# Microcontroller.net
KiCad netlist of a schematic drawn in Altium Designer
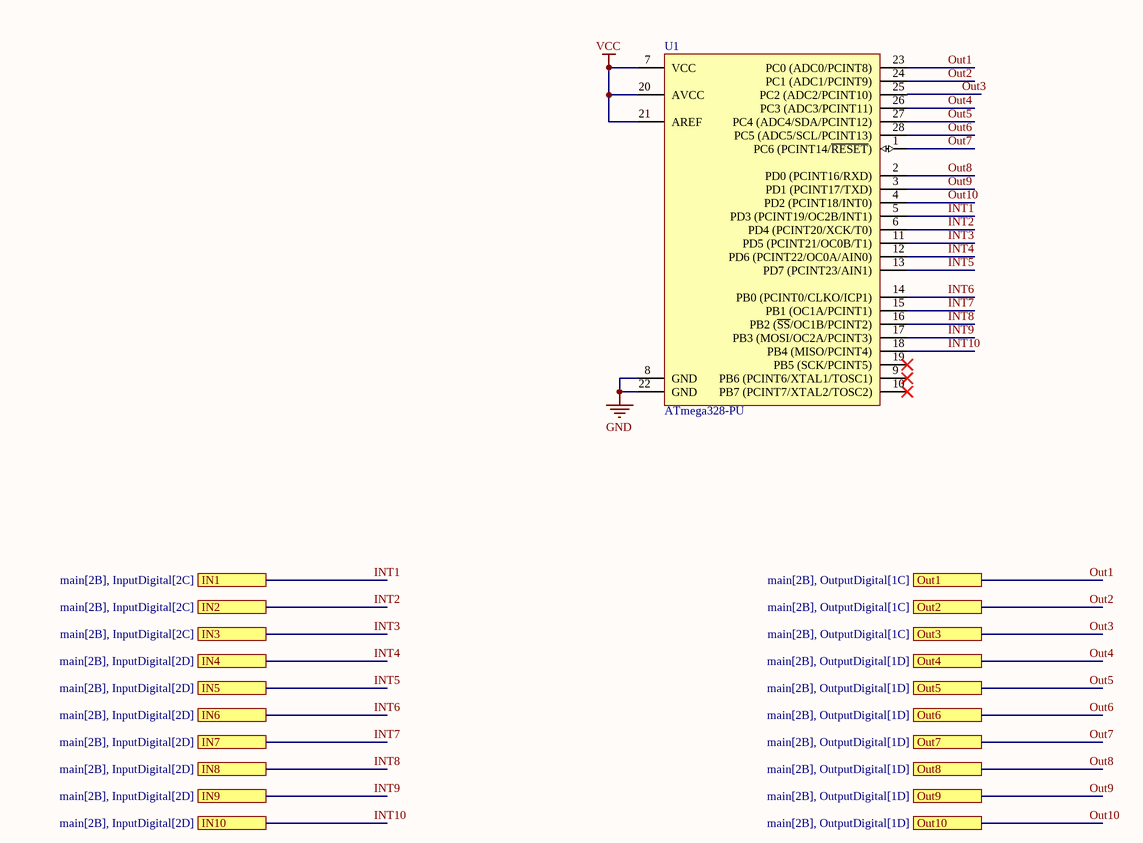
[diagram p0: Microcontroller.SchDoc]

(export (version "E")
  (design (tool "Eeschema 10.0.6"))
  (components
    (comp (ref "U1")
      (value "ATmega328-PU")
      (footprint "28P3")
      (libsource (lib "Ejemplo2") (part "CMP-0095-00015-2"))
    )
  )
  (nets
    (net (code "1") (name "/INT1") (class "Default")
      (node (ref "U1") (pin "5") (pinfunction "PD3_(PCINT19/OC2B/INT1)_5") (pintype "passive"))
    )
    (net (code "2") (name "/INT2") (class "Default")
      (node (ref "U1") (pin "6") (pinfunction "PD4_(PCINT20/XCK/T0)_6") (pintype "passive"))
    )
    (net (code "3") (name "/INT3") (class "Default")
      (node (ref "U1") (pin "11") (pinfunction "PD5_(PCINT21/OC0B/T1)_11") (pintype "passive"))
    )
    (net (code "4") (name "/INT4") (class "Default")
      (node (ref "U1") (pin "12") (pinfunction "PD6_(PCINT22/OC0A/AIN0)_12") (pintype "passive"))
    )
    (net (code "5") (name "/INT5") (class "Default")
      (node (ref "U1") (pin "13") (pinfunction "PD7_(PCINT23/AIN1)_13") (pintype "passive"))
    )
    (net (code "6") (name "/INT6") (class "Default")
      (node (ref "U1") (pin "14") (pinfunction "PB0_(PCINT0/CLKO/ICP1)_14") (pintype "passive"))
    )
    (net (code "7") (name "/INT7") (class "Default")
      (node (ref "U1") (pin "15") (pinfunction "PB1_(OC1A/PCINT1)_15") (pintype "passive"))
    )
    (net (code "8") (name "/INT8") (class "Default")
      (node (ref "U1") (pin "16") (pinfunction "PB2_(~{SS}/OC1B/PCINT2)_16") (pintype "passive"))
    )
    (net (code "9") (name "/INT9") (class "Default")
      (node (ref "U1") (pin "17") (pinfunction "PB3_(MOSI/OC2A/PCINT3)_17") (pintype "passive"))
    )
    (net (code "10") (name "/INT10") (class "Default")
      (node (ref "U1") (pin "18") (pinfunction "PB4_(MISO/PCINT4)_18") (pintype "passive"))
    )
    (net (code "11") (name "/Out1") (class "Default")
      (node (ref "U1") (pin "23") (pinfunction "PC0_(ADC0/PCINT8)_23") (pintype "passive"))
    )
    (net (code "12") (name "/Out2") (class "Default")
      (node (ref "U1") (pin "24") (pinfunction "PC1_(ADC1/PCINT9)_24") (pintype "passive"))
    )
    (net (code "13") (name "/Out3") (class "Default")
      (node (ref "U1") (pin "25") (pinfunction "PC2_(ADC2/PCINT10)_25") (pintype "passive"))
    )
    (net (code "14") (name "/Out4") (class "Default")
      (node (ref "U1") (pin "26") (pinfunction "PC3_(ADC3/PCINT11)_26") (pintype "passive"))
    )
    (net (code "15") (name "/Out5") (class "Default")
      (node (ref "U1") (pin "27") (pinfunction "PC4_(ADC4/SDA/PCINT12)_27") (pintype "passive"))
    )
    (net (code "16") (name "/Out6") (class "Default")
      (node (ref "U1") (pin "28") (pinfunction "PC5_(ADC5/SCL/PCINT13)_28") (pintype "passive"))
    )
    (net (code "17") (name "/Out7") (class "Default")
      (node (ref "U1") (pin "1") (pinfunction "PC6_(PCINT14/~{RESET})_1") (pintype "bidirectional"))
    )
    (net (code "18") (name "/Out8") (class "Default")
      (node (ref "U1") (pin "2") (pinfunction "PD0_(PCINT16/RXD)_2") (pintype "passive"))
    )
    (net (code "19") (name "/Out9") (class "Default")
      (node (ref "U1") (pin "3") (pinfunction "PD1_(PCINT17/TXD)_3") (pintype "passive"))
    )
    (net (code "20") (name "/Out10") (class "Default")
      (node (ref "U1") (pin "4") (pinfunction "PD2_(PCINT18/INT0)_4") (pintype "passive"))
    )
    (net (code "21") (name "GND") (class "Default")
      (node (ref "U1") (pin "22") (pinfunction "GND_22") (pintype "power_in"))
      (node (ref "U1") (pin "8") (pinfunction "GND_8") (pintype "power_in"))
    )
    (net (code "22") (name "VCC") (class "Default")
      (node (ref "U1") (pin "20") (pinfunction "AVCC_20") (pintype "power_in"))
      (node (ref "U1") (pin "21") (pinfunction "AREF_21") (pintype "power_in"))
      (node (ref "U1") (pin "7") (pinfunction "VCC_7") (pintype "power_in"))
    )
    (net (code "23") (name "unconnected-(U1-PB5_(SCK{slash}PCINT5)-Pad19)") (class "Default")
      (node (ref "U1") (pin "19") (pinfunction "PB5_(SCK/PCINT5)_19") (pintype "passive+no_connect"))
    )
    (net (code "24") (name "unconnected-(U1-PB6_(PCINT6{slash}XTAL1{slash}TOSC1)-Pad9)") (class "Default")
      (node (ref "U1") (pin "9") (pinfunction "PB6_(PCINT6/XTAL1/TOSC1)_9") (pintype "passive+no_connect"))
    )
    (net (code "25") (name "unconnected-(U1-PB7_(PCINT7{slash}XTAL2{slash}TOSC2)-Pad10)") (class "Default")
      (node (ref "U1") (pin "10") (pinfunction "PB7_(PCINT7/XTAL2/TOSC2)_10") (pintype "passive+no_connect"))
    )
  )
)
